# LKS_EVB_MVPOW_V4_0.net
KiCad netlist of a schematic drawn in Altium Designer
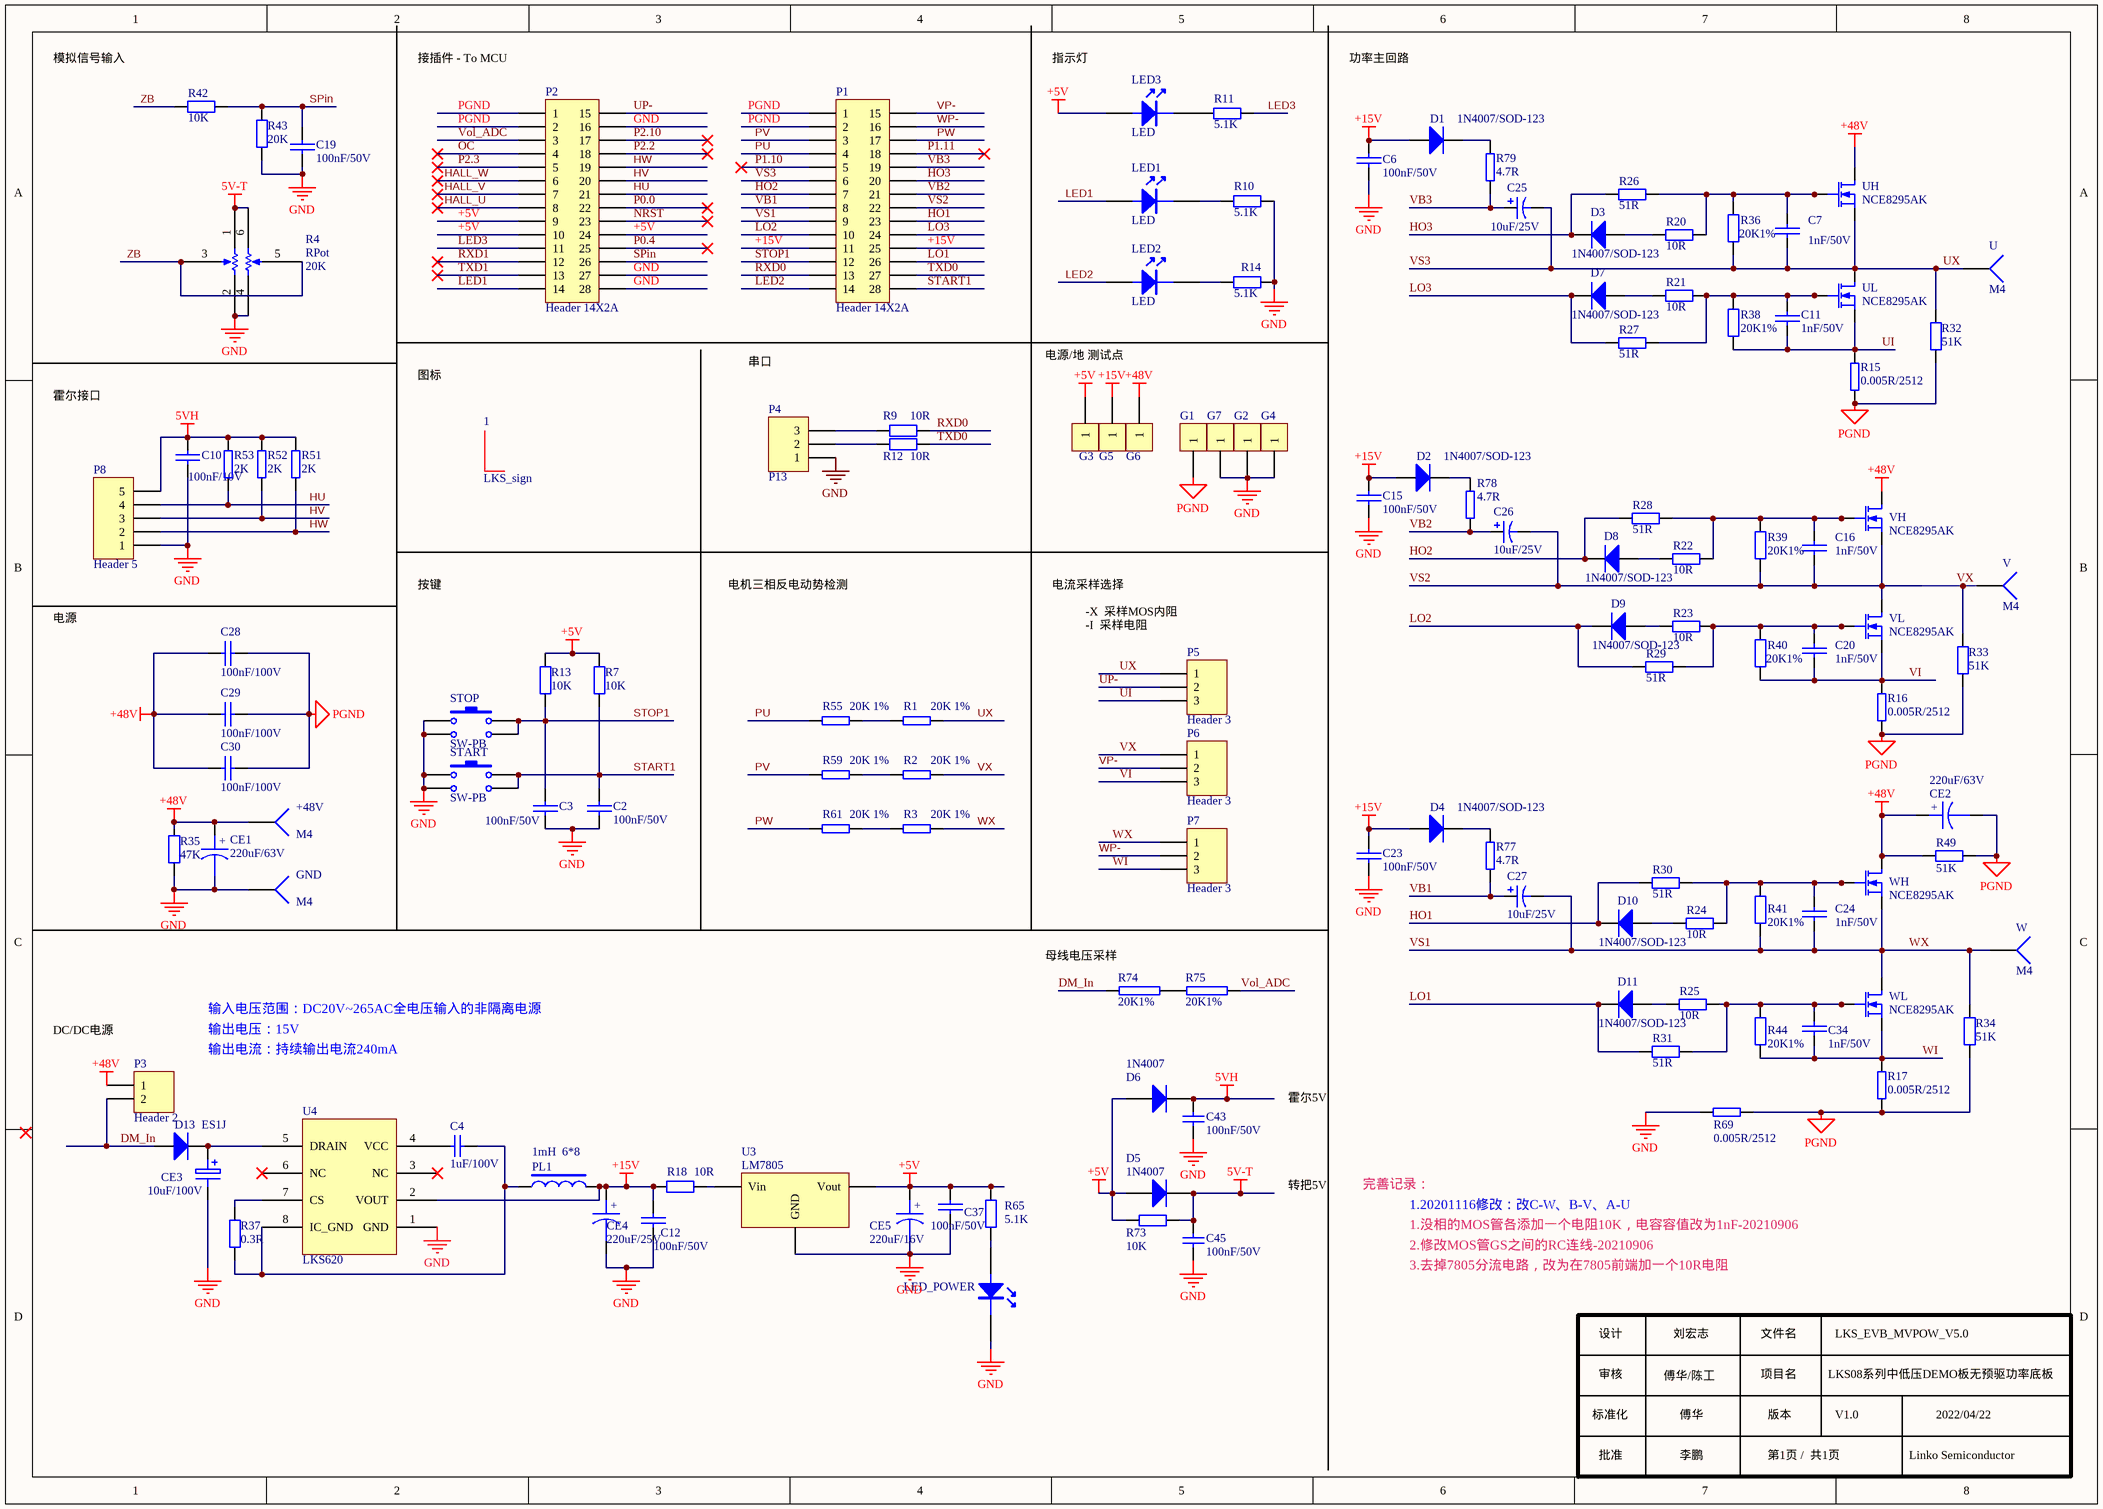
[diagram p0: LKS_EVB_MVPOW_V4.0.SchDoc]

(export (version "E")
  (design (tool "Eeschema 10.0.6"))
  (components
    (comp (ref "+48V")
      (value "M4")
      (footprint "M4_Conector")
      (description "Socket")
      (fields (field (name "PUBLISHER") "Altium Limited"))
      (libsource (lib "*") (part "Socket"))
    )
    (comp (ref "1")
      (value "LKS_sign")
      (footprint "LKS_LOGO2")
      (libsource (lib "linko sch library") (part "LKS_sign"))
    )
    (comp (ref "C2")
      (value "100nF/50V")
      (footprint "0603C")
      (description "Capacitor")
      (libsource (lib "GJ-BC-IC") (part "CAP"))
    )
    (comp (ref "C3")
      (value "100nF/50V")
      (footprint "0603C")
      (description "Capacitor")
      (libsource (lib "GJ-BC-IC") (part "CAP"))
    )
    (comp (ref "C4")
      (value "1uF/100V")
      (footprint "1206")
      (description "Capacitor")
      (fields (field (name "PUBLISHER") "Altium Limited"))
      (libsource (lib "Miscellaneous Devices") (part "Cap"))
    )
    (comp (ref "C6")
      (value "100nF/50V")
      (footprint "0603C")
      (description "Capacitor")
      (libsource (lib "*") (part "C"))
    )
    (comp (ref "C7")
      (value "1nF/50V")
      (footprint "0603C")
      (description "Capacitor")
      (libsource (lib "*") (part "CAP"))
    )
    (comp (ref "C10")
      (value "100nF/10V")
      (footprint "0603C")
      (description "Capacitor")
      (libsource (lib "GJ-BC-IC") (part "CAP"))
    )
    (comp (ref "C11")
      (value "1nF/50V")
      (footprint "0603C")
      (description "Capacitor")
      (libsource (lib "*") (part "CAP"))
    )
    (comp (ref "C12")
      (value "100nF/50V")
      (footprint "0603C")
      (description "Capacitor")
      (libsource (lib "") (part "CAP_1"))
    )
    (comp (ref "C15")
      (value "100nF/50V")
      (footprint "0603C")
      (description "Capacitor")
      (libsource (lib "*") (part "C"))
    )
    (comp (ref "C16")
      (value "1nF/50V")
      (footprint "0603C")
      (description "Capacitor")
      (libsource (lib "*") (part "CAP"))
    )
    (comp (ref "C19")
      (value "100nF/50V")
      (footprint "0603C")
      (description "Capacitor")
      (libsource (lib "*") (part "C"))
    )
    (comp (ref "C20")
      (value "1nF/50V")
      (footprint "0603C")
      (description "Capacitor")
      (libsource (lib "*") (part "CAP"))
    )
    (comp (ref "C23")
      (value "100nF/50V")
      (footprint "0603C")
      (description "Capacitor")
      (libsource (lib "*") (part "C"))
    )
    (comp (ref "C24")
      (value "1nF/50V")
      (footprint "0603C")
      (description "Capacitor")
      (libsource (lib "*") (part "CAP"))
    )
    (comp (ref "C25")
      (value "10uF/25V")
      (footprint "1206")
      (description "Polarized Capacitor (Radial)")
      (fields (field (name "PUBLISHER") "Altium Limited"))
      (libsource (lib "*") (part "Cap Pol1"))
    )
    (comp (ref "C26")
      (value "10uF/25V")
      (footprint "1206")
      (description "Polarized Capacitor (Radial)")
      (fields (field (name "PUBLISHER") "Altium Limited"))
      (libsource (lib "*") (part "Cap Pol1"))
    )
    (comp (ref "C27")
      (value "10uF/25V")
      (footprint "1206")
      (description "Polarized Capacitor (Radial)")
      (fields (field (name "PUBLISHER") "Altium Limited"))
      (libsource (lib "*") (part "Cap Pol1"))
    )
    (comp (ref "C28")
      (value "100nF/100V")
      (footprint "0805C")
      (description "Capacitor")
      (libsource (lib "") (part "CAP_1"))
    )
    (comp (ref "C29")
      (value "100nF/100V")
      (footprint "0805C")
      (description "Capacitor")
      (libsource (lib "") (part "CAP_1"))
    )
    (comp (ref "C30")
      (value "100nF/100V")
      (footprint "0805C")
      (description "Capacitor")
      (libsource (lib "") (part "CAP_1"))
    )
    (comp (ref "C34")
      (value "1nF/50V")
      (footprint "0603C")
      (description "Capacitor")
      (libsource (lib "*") (part "CAP"))
    )
    (comp (ref "C37")
      (value "100nF/50V")
      (footprint "0603C")
      (description "Capacitor")
      (libsource (lib "*") (part "C"))
    )
    (comp (ref "C43")
      (value "100nF/50V")
      (footprint "0603C")
      (description "Capacitor")
      (fields (field (name "PUBLISHER") "Altium Limited"))
      (libsource (lib "Miscellaneous Devices") (part "Cap"))
    )
    (comp (ref "C45")
      (value "100nF/50V")
      (footprint "0603C")
      (description "Capacitor")
      (fields (field (name "PUBLISHER") "Altium Limited"))
      (libsource (lib "Miscellaneous Devices") (part "Cap"))
    )
    (comp (ref "CE1")
      (value "220uF/63V")
      (footprint "220UF/63V 12.5*12.5")
      (description "Capacitor---电解电容")
      (libsource (lib "LINKO_V1.0") (part "Capacitor Pol"))
    )
    (comp (ref "CE2")
      (value "220uF/63V")
      (footprint "220UF/63V 12.5*12.5")
      (description "Capacitor---电解电容")
      (libsource (lib "LINKO_V1.0") (part "Capacitor Pol"))
    )
    (comp (ref "CE3")
      (value "10uF/100V")
      (footprint "220UF/25V paster8*10")
      (description "Electrolytic Capacitor")
      (libsource (lib "*") (part "CD"))
    )
    (comp (ref "CE4")
      (value "220uF/25V")
      (footprint "220UF/25V 8*10")
      (description "Capacitor---电解电容")
      (libsource (lib "LINKO_V1.0") (part "Capacitor Pol"))
    )
    (comp (ref "CE5")
      (value "220uF/16V")
      (footprint "220UF/16V 6.3*7.7")
      (description "Capacitor---电解电容")
      (libsource (lib "LINKO_V1.0") (part "Capacitor Pol"))
    )
    (comp (ref "D1")
      (value "1N4007/SOD-123")
      (footprint "SOD123")
      (description "Default Diode")
      (fields (field (name "PUBLISHER") "Altium Limited"))
      (libsource (lib "*") (part "Diode"))
    )
    (comp (ref "D2")
      (value "1N4007/SOD-123")
      (footprint "SOD123")
      (description "Default Diode")
      (fields (field (name "PUBLISHER") "Altium Limited"))
      (libsource (lib "*") (part "Diode"))
    )
    (comp (ref "D3")
      (value "1N4007/SOD-123")
      (footprint "SOD123")
      (description "Default Diode")
      (fields (field (name "PUBLISHER") "Altium Limited"))
      (libsource (lib "*") (part "Diode"))
    )
    (comp (ref "D4")
      (value "1N4007/SOD-123")
      (footprint "SOD123")
      (description "Default Diode")
      (fields (field (name "PUBLISHER") "Altium Limited"))
      (libsource (lib "*") (part "Diode"))
    )
    (comp (ref "D5")
      (value "1N4007")
      (footprint "D1206")
      (description "1 Amp General Purpose Rectifier")
      (fields (field (name "PUBLISHER") "Altium Limited"))
      (libsource (lib "Miscellaneous Devices") (part "Diode 1N4007"))
    )
    (comp (ref "D6")
      (value "1N4007")
      (footprint "D1206")
      (description "1 Amp General Purpose Rectifier")
      (fields (field (name "PUBLISHER") "Altium Limited"))
      (libsource (lib "Miscellaneous Devices") (part "Diode 1N4007"))
    )
    (comp (ref "D7")
      (value "1N4007/SOD-123")
      (footprint "SOD123")
      (description "Default Diode")
      (fields (field (name "PUBLISHER") "Altium Limited"))
      (libsource (lib "*") (part "Diode"))
    )
    (comp (ref "D8")
      (value "1N4007/SOD-123")
      (footprint "SOD123")
      (description "Default Diode")
      (fields (field (name "PUBLISHER") "Altium Limited"))
      (libsource (lib "*") (part "Diode"))
    )
    (comp (ref "D9")
      (value "1N4007/SOD-123")
      (footprint "SOD123")
      (description "Default Diode")
      (fields (field (name "PUBLISHER") "Altium Limited"))
      (libsource (lib "*") (part "Diode"))
    )
    (comp (ref "D10")
      (value "1N4007/SOD-123")
      (footprint "SOD123")
      (description "Default Diode")
      (fields (field (name "PUBLISHER") "Altium Limited"))
      (libsource (lib "*") (part "Diode"))
    )
    (comp (ref "D11")
      (value "1N4007/SOD-123")
      (footprint "SOD123")
      (description "Default Diode")
      (fields (field (name "PUBLISHER") "Altium Limited"))
      (libsource (lib "*") (part "Diode"))
    )
    (comp (ref "D13")
      (value "ES1J")
      (footprint "DO-214AC")
      (description "Default Diode")
      (fields (field (name "PUBLISHER") "Altium Limited"))
      (libsource (lib "*") (part "Diode"))
    )
    (comp (ref "G1")
      (value "PAD1.2")
      (footprint "PAD1.2")
      (description "Connector")
      (libsource (lib "*") (part "CON1"))
    )
    (comp (ref "G2")
      (value "PAD1.2")
      (footprint "PAD1.2")
      (description "Connector")
      (libsource (lib "*") (part "CON1"))
    )
    (comp (ref "G3")
      (value "PAD1.2")
      (footprint "PAD1.2")
      (description "Connector")
      (libsource (lib "") (part "CON1_1"))
    )
    (comp (ref "G4")
      (value "PAD1.2")
      (footprint "PAD1.2")
      (description "Connector")
      (libsource (lib "*") (part "CON1"))
    )
    (comp (ref "G5")
      (value "PAD1.2")
      (footprint "PAD1.2")
      (description "Connector")
      (libsource (lib "") (part "CON1_1"))
    )
    (comp (ref "G6")
      (value "PAD1.2")
      (footprint "PAD1.2")
      (description "Connector")
      (libsource (lib "") (part "CON1_1"))
    )
    (comp (ref "G7")
      (value "PAD1.2")
      (footprint "PAD1.2")
      (description "Connector")
      (libsource (lib "*") (part "CON1"))
    )
    (comp (ref "GND")
      (value "M4")
      (footprint "M4_Conector")
      (description "Socket")
      (fields (field (name "PUBLISHER") "Altium Limited"))
      (libsource (lib "*") (part "Socket"))
    )
    (comp (ref "LED1") (value "LED") (footprint "SOD323") (libsource (lib "GJ-BC-IC") (part "LED")))
    (comp (ref "LED2") (value "LED") (footprint "SOD323") (libsource (lib "GJ-BC-IC") (part "LED")))
    (comp (ref "LED3") (value "LED") (footprint "SOD323") (libsource (lib "GJ-BC-IC") (part "LED")))
    (comp (ref "LED_POWER") (value "LED_R") (footprint "SOD323") (libsource (lib "*") (part "LED")))
    (comp (ref "P1")
      (value "Header 14X2A")
      (footprint "HDR2X14_CEN")
      (description "Header, 14-Pin, Dual row")
      (fields (field (name "PUBLISHER") "Altium Limited"))
      (libsource (lib "Miscellaneous Connectors") (part "Header 14X2A"))
    )
    (comp (ref "P2")
      (value "Header 14X2A")
      (footprint "HDR2X14_CEN")
      (description "Header, 14-Pin, Dual row")
      (fields (field (name "PUBLISHER") "Altium Limited"))
      (libsource (lib "Miscellaneous Connectors") (part "Header 14X2A"))
    )
    (comp (ref "P3")
      (value "Header 2")
      (footprint "HDR1X2")
      (description "Header, 2-Pin")
      (fields (field (name "PUBLISHER") "Altium Limited"))
      (libsource (lib "Miscellaneous Connectors") (part "Header 2"))
    )
    (comp (ref "P4")
      (value "P13")
      (footprint "2.54-XH-3A-180")
      (description "Header, 3-Pin")
      (fields (field (name "PUBLISHER") "Altium Limited"))
      (libsource (lib "") (part "Header 3_1"))
    )
    (comp (ref "P5")
      (value "Header 3")
      (footprint "HDR1X3")
      (description "Header, 3-Pin")
      (fields (field (name "PUBLISHER") "Altium Limited"))
      (libsource (lib "Miscellaneous Connectors") (part "Header 3"))
    )
    (comp (ref "P6")
      (value "Header 3")
      (footprint "HDR1X3")
      (description "Header, 3-Pin")
      (fields (field (name "PUBLISHER") "Altium Limited"))
      (libsource (lib "Miscellaneous Connectors") (part "Header 3"))
    )
    (comp (ref "P7")
      (value "Header 3")
      (footprint "HDR1X3")
      (description "Header, 3-Pin")
      (fields (field (name "PUBLISHER") "Altium Limited"))
      (libsource (lib "Miscellaneous Connectors") (part "Header 3"))
    )
    (comp (ref "P8")
      (value "Header 5")
      (footprint "2.54-XH-5A-180")
      (description "Header, 5-Pin")
      (fields (field (name "PUBLISHER") "Altium Limited"))
      (libsource (lib "Miscellaneous Connectors") (part "Header 5"))
    )
    (comp (ref "PL1") (value "1mH  6*8") (footprint "L_DIP_6*8MM") (libsource (lib "*") (part "L")))
    (comp (ref "R1") (value "20K 1%") (footprint "0805R") (libsource (lib "HenterLi") (part "RES/1")))
    (comp (ref "R2") (value "20K 1%") (footprint "0805R") (libsource (lib "HenterLi") (part "RES/1")))
    (comp (ref "R3") (value "20K 1%") (footprint "0805R") (libsource (lib "HenterLi") (part "RES/1")))
    (comp (ref "R4")
      (value "RPot")
      (footprint "RK097-W-1")
      (description "Potentiometer")
      (fields (field (name "ALTIUM_VALUE") "20K") (field (name "PUBLISHER") "Altium Limited"))
      (libsource (lib "LKS_DEMO_V5.0") (part "RPot"))
    )
    (comp (ref "R7")
      (value "10K")
      (footprint "0603R")
      (description "Resistor")
      (fields (field (name "PUBLISHER") "Altium Limited"))
      (libsource (lib "") (part "Res2_1"))
    )
    (comp (ref "R9")
      (value "10R")
      (footprint "0603R")
      (description "Resistor")
      (fields (field (name "PUBLISHER") "Altium Limited"))
      (libsource (lib "Miscellaneous Devices") (part "Res2"))
    )
    (comp (ref "R10")
      (value "5.1K")
      (footprint "0603R")
      (description "Resistor")
      (fields (field (name "PUBLISHER") "Altium Limited"))
      (libsource (lib "") (part "Res2_2"))
    )
    (comp (ref "R11")
      (value "5.1K")
      (footprint "0603R")
      (description "Resistor")
      (fields (field (name "PUBLISHER") "Altium Limited"))
      (libsource (lib "") (part "Res2_2"))
    )
    (comp (ref "R12")
      (value "10R")
      (footprint "0603R")
      (description "Resistor")
      (fields (field (name "PUBLISHER") "Altium Limited"))
      (libsource (lib "") (part "Res2_1"))
    )
    (comp (ref "R13")
      (value "10K")
      (footprint "0603R")
      (description "Resistor")
      (fields (field (name "PUBLISHER") "Altium Limited"))
      (libsource (lib "GJ-BC-IC") (part "Res2"))
    )
    (comp (ref "R14")
      (value "5.1K")
      (footprint "0603R")
      (description "Resistor")
      (fields (field (name "PUBLISHER") "Altium Limited"))
      (libsource (lib "") (part "Res2_2"))
    )
    (comp (ref "R15") (value "0.005R/2512") (footprint "2512") (libsource (lib "*") (part "RES2短")))
    (comp (ref "R16") (value "0.005R/2512") (footprint "2512") (libsource (lib "*") (part "RES2短")))
    (comp (ref "R17") (value "0.005R/2512") (footprint "2512") (libsource (lib "*") (part "RES2短")))
    (comp (ref "R18")
      (value "10R")
      (footprint "1206R")
      (description "Resistor")
      (fields (field (name "PUBLISHER") "Altium Limited"))
      (libsource (lib "LINKO_V1.0") (part "Res"))
    )
    (comp (ref "R20")
      (value "10R")
      (footprint "0805R")
      (description "Resistor")
      (fields (field (name "PUBLISHER") "Altium Limited"))
      (libsource (lib "") (part "1Res_1"))
    )
    (comp (ref "R21")
      (value "10R")
      (footprint "0805R")
      (description "Resistor")
      (fields (field (name "PUBLISHER") "Altium Limited"))
      (libsource (lib "") (part "1Res_1"))
    )
    (comp (ref "R22")
      (value "10R")
      (footprint "0805R")
      (description "Resistor")
      (fields (field (name "PUBLISHER") "Altium Limited"))
      (libsource (lib "") (part "1Res_1"))
    )
    (comp (ref "R23")
      (value "10R")
      (footprint "0805R")
      (description "Resistor")
      (fields (field (name "PUBLISHER") "Altium Limited"))
      (libsource (lib "") (part "1Res_1"))
    )
    (comp (ref "R24")
      (value "10R")
      (footprint "0805R")
      (description "Resistor")
      (fields (field (name "PUBLISHER") "Altium Limited"))
      (libsource (lib "") (part "1Res_1"))
    )
    (comp (ref "R25")
      (value "10R")
      (footprint "0805R")
      (description "Resistor")
      (fields (field (name "PUBLISHER") "Altium Limited"))
      (libsource (lib "") (part "1Res_1"))
    )
    (comp (ref "R26")
      (value "51R")
      (footprint "0805R")
      (description "Resistor")
      (fields (field (name "PUBLISHER") "Altium Limited"))
      (libsource (lib "LINKO_V1.0") (part "Res"))
    )
    (comp (ref "R27")
      (value "51R")
      (footprint "0805R")
      (description "Resistor")
      (fields (field (name "PUBLISHER") "Altium Limited"))
      (libsource (lib "LINKO_V1.0") (part "1Res"))
    )
    (comp (ref "R28")
      (value "51R")
      (footprint "0805R")
      (description "Resistor")
      (fields (field (name "PUBLISHER") "Altium Limited"))
      (libsource (lib "LINKO_V1.0") (part "1Res"))
    )
    (comp (ref "R29")
      (value "51R")
      (footprint "0805R")
      (description "Resistor")
      (fields (field (name "PUBLISHER") "Altium Limited"))
      (libsource (lib "LINKO_V1.0") (part "1Res"))
    )
    (comp (ref "R30")
      (value "51R")
      (footprint "0805R")
      (description "Resistor")
      (fields (field (name "PUBLISHER") "Altium Limited"))
      (libsource (lib "LINKO_V1.0") (part "1Res"))
    )
    (comp (ref "R31")
      (value "51R")
      (footprint "0805R")
      (description "Resistor")
      (fields (field (name "PUBLISHER") "Altium Limited"))
      (libsource (lib "LINKO_V1.0") (part "1Res"))
    )
    (comp (ref "R32")
      (value "51K")
      (footprint "0805R")
      (description "Resistor")
      (fields (field (name "PUBLISHER") "Altium Limited"))
      (libsource (lib "") (part "1Res_2"))
    )
    (comp (ref "R33")
      (value "51K")
      (footprint "0805R")
      (description "Resistor")
      (fields (field (name "PUBLISHER") "Altium Limited"))
      (libsource (lib "") (part "1Res_2"))
    )
    (comp (ref "R34")
      (value "51K")
      (footprint "0805R")
      (description "Resistor")
      (fields (field (name "PUBLISHER") "Altium Limited"))
      (libsource (lib "") (part "1Res_2"))
    )
    (comp (ref "R35")
      (value "47K")
      (footprint "1206R")
      (description "Resistor")
      (fields (field (name "PUBLISHER") "Altium Limited"))
      (libsource (lib "") (part "Res_2"))
    )
    (comp (ref "R36")
      (value "20K1%")
      (footprint "0603R")
      (description "Resistor")
      (fields (field (name "PUBLISHER") "Altium Limited"))
      (libsource (lib "") (part "Res_1"))
    )
    (comp (ref "R37")
      (value "0.3R")
      (footprint "1206")
      (description "Resistor")
      (fields (field (name "PUBLISHER") "Altium Limited"))
      (libsource (lib "") (part "Res2_1"))
    )
    (comp (ref "R38")
      (value "20K1%")
      (footprint "0603R")
      (description "Resistor")
      (fields (field (name "PUBLISHER") "Altium Limited"))
      (libsource (lib "") (part "Res_1"))
    )
    (comp (ref "R39")
      (value "20K1%")
      (footprint "0603R")
      (description "Resistor")
      (fields (field (name "PUBLISHER") "Altium Limited"))
      (libsource (lib "") (part "Res_1"))
    )
    (comp (ref "R40")
      (value "20K1%")
      (footprint "0603R")
      (description "Resistor")
      (fields (field (name "PUBLISHER") "Altium Limited"))
      (libsource (lib "") (part "Res_1"))
    )
    (comp (ref "R41")
      (value "20K1%")
      (footprint "0603R")
      (description "Resistor")
      (fields (field (name "PUBLISHER") "Altium Limited"))
      (libsource (lib "") (part "Res_1"))
    )
    (comp (ref "R42")
      (value "10K")
      (footprint "0603R")
      (description "Resistor")
      (fields (field (name "PUBLISHER") "Altium Limited"))
      (libsource (lib "LINKO_V1.0") (part "Res"))
    )
    (comp (ref "R43")
      (value "20K")
      (footprint "0603R")
      (description "Resistor")
      (fields (field (name "PUBLISHER") "Altium Limited"))
      (libsource (lib "") (part "Res_1"))
    )
    (comp (ref "R44")
      (value "20K1%")
      (footprint "0603R")
      (description "Resistor")
      (fields (field (name "PUBLISHER") "Altium Limited"))
      (libsource (lib "") (part "Res_1"))
    )
    (comp (ref "R49")
      (value "51K")
      (footprint "0805R")
      (description "Resistor")
      (fields (field (name "PUBLISHER") "Altium Limited"))
      (libsource (lib "LINKO_V1.0") (part "1Res"))
    )
    (comp (ref "R51") (value "2K") (footprint "0603R") (libsource (lib "") (part "RES/1_1")))
    (comp (ref "R52") (value "2K") (footprint "0603R") (libsource (lib "") (part "RES/1_1")))
    (comp (ref "R53") (value "2K") (footprint "0603R") (libsource (lib "") (part "RES/1_1")))
    (comp (ref "R55") (value "20K 1%") (footprint "0805R") (libsource (lib "HenterLi") (part "RES/1")))
    (comp (ref "R59") (value "20K 1%") (footprint "0805R") (libsource (lib "HenterLi") (part "RES/1")))
    (comp (ref "R61") (value "20K 1%") (footprint "0805R") (libsource (lib "HenterLi") (part "RES/1")))
    (comp (ref "R65")
      (value "5.1K")
      (footprint "0603R")
      (description "Resistor")
      (fields (field (name "PUBLISHER") "Altium Limited"))
      (libsource (lib "Miscellaneous Devices") (part "Res2"))
    )
    (comp (ref "R69") (value "0.005R/2512") (footprint "2512") (libsource (lib "*") (part "RES2短")))
    (comp (ref "R73")
      (value "10K")
      (footprint "0603R")
      (description "Resistor")
      (fields (field (name "PUBLISHER") "Altium Limited"))
      (libsource (lib "") (part "Res2_2"))
    )
    (comp (ref "R74") (value "20K1%") (footprint "0603R") (libsource (lib "*") (part "R")))
    (comp (ref "R75") (value "20K1%") (footprint "0603R") (libsource (lib "*") (part "R")))
    (comp (ref "R77") (value "4.7R") (footprint "0805r") (libsource (lib "*") (part "RES2短")))
    (comp (ref "R78") (value "4.7R") (footprint "0805r") (libsource (lib "*") (part "RES2短")))
    (comp (ref "R79") (value "4.7R") (footprint "0805r") (libsource (lib "*") (part "RES2短")))
    (comp (ref "START")
      (value "SW-PB")
      (footprint "SW-PB  12*12")
      (description "Switch")
      (fields (field (name "PUBLISHER") "Altium Limited"))
      (libsource (lib "LKS_DEMO_081_V4.0") (part "SW-PB"))
    )
    (comp (ref "STOP")
      (value "SW-PB")
      (footprint "SW-PB  12*12")
      (description "Switch")
      (fields (field (name "PUBLISHER") "Altium Limited"))
      (libsource (lib "LKS_DEMO_081_V4.0") (part "SW-PB"))
    )
    (comp (ref "U")
      (value "M4")
      (footprint "M4_Conector")
      (description "Socket")
      (fields (field (name "PUBLISHER") "Altium Limited"))
      (libsource (lib "*") (part "Socket"))
    )
    (comp (ref "U3")
      (value "LM7805")
      (footprint "linko pcb library:SOT-89")
      (libsource (lib "*") (part "VOL-78"))
    )
    (comp (ref "U4") (value "LKS620") (footprint "SO-8") (libsource (lib "081-620") (part "LKS620")))
    (comp (ref "UH")
      (value "NCE8295AK")
      (footprint "TO-252")
      (libsource (lib "POWER-conponent") (part "MOS"))
    )
    (comp (ref "UL")
      (value "NCE8295AK")
      (footprint "TO-252")
      (libsource (lib "POWER-conponent") (part "MOS"))
    )
    (comp (ref "V")
      (value "M4")
      (footprint "M4_Conector")
      (description "Socket")
      (fields (field (name "PUBLISHER") "Altium Limited"))
      (libsource (lib "*") (part "Socket"))
    )
    (comp (ref "VH")
      (value "NCE8295AK")
      (footprint "TO-252")
      (libsource (lib "POWER-conponent") (part "MOS"))
    )
    (comp (ref "VL")
      (value "NCE8295AK")
      (footprint "TO-252")
      (libsource (lib "POWER-conponent") (part "MOS"))
    )
    (comp (ref "W")
      (value "M4")
      (footprint "M4_Conector")
      (description "Socket")
      (fields (field (name "PUBLISHER") "Altium Limited"))
      (libsource (lib "*") (part "Socket"))
    )
    (comp (ref "WH")
      (value "NCE8295AK")
      (footprint "TO-252")
      (libsource (lib "POWER-conponent") (part "MOS"))
    )
    (comp (ref "WL")
      (value "NCE8295AK")
      (footprint "TO-252")
      (libsource (lib "POWER-conponent") (part "MOS"))
    )
  )
  (nets
    (net (code "1") (name "+5V") (class "Default")
      (node (ref "C37") (pin "2") (pinfunction "2_2") (pintype "passive"))
      (node (ref "CE5") (pin "1") (pinfunction "1_1") (pintype "passive"))
      (node (ref "D5") (pin "1") (pinfunction "A_1") (pintype "passive"))
      (node (ref "D6") (pin "1") (pinfunction "A_1") (pintype "passive"))
      (node (ref "G3") (pin "1") (pinfunction "1_1") (pintype "passive"))
      (node (ref "LED3") (pin "1") (pinfunction "A_1") (pintype "passive"))
      (node (ref "P2") (pin "10") (pinfunction "10_10") (pintype "passive"))
      (node (ref "P2") (pin "24") (pinfunction "24_24") (pintype "passive"))
      (node (ref "P2") (pin "9") (pinfunction "9_9") (pintype "passive"))
      (node (ref "R13") (pin "2") (pinfunction "2_2") (pintype "passive"))
      (node (ref "R65") (pin "1") (pinfunction "1_1") (pintype "passive"))
      (node (ref "R7") (pin "1") (pinfunction "1_1") (pintype "passive"))
      (node (ref "R73") (pin "1") (pinfunction "1_1") (pintype "passive"))
      (node (ref "U3") (pin "1") (pinfunction "Vout_1") (pintype "passive"))
    )
    (net (code "2") (name "+15V") (class "Default")
      (node (ref "C12") (pin "1") (pinfunction "1_1") (pintype "passive"))
      (node (ref "C15") (pin "2") (pinfunction "2_2") (pintype "passive"))
      (node (ref "C23") (pin "2") (pinfunction "2_2") (pintype "passive"))
      (node (ref "C6") (pin "2") (pinfunction "2_2") (pintype "passive"))
      (node (ref "CE4") (pin "1") (pinfunction "1_1") (pintype "passive"))
      (node (ref "D1") (pin "1") (pinfunction "A_1") (pintype "passive"))
      (node (ref "D2") (pin "1") (pinfunction "A_1") (pintype "passive"))
      (node (ref "D4") (pin "1") (pinfunction "A_1") (pintype "passive"))
      (node (ref "G5") (pin "1") (pinfunction "1_1") (pintype "passive"))
      (node (ref "P1") (pin "11") (pinfunction "11_11") (pintype "passive"))
      (node (ref "P1") (pin "25") (pinfunction "25_25") (pintype "passive"))
      (node (ref "PL1") (pin "1") (pinfunction "1_1") (pintype "passive"))
      (node (ref "R18") (pin "1") (pinfunction "1_1") (pintype "passive"))
      (node (ref "U4") (pin "2") (pinfunction "VOUT_2") (pintype "passive"))
    )
    (net (code "3") (name "+48V") (class "Default")
      (node (ref "+48V") (pin "1") (pinfunction "1_1") (pintype "passive"))
      (node (ref "C28") (pin "2") (pinfunction "2_2") (pintype "passive"))
      (node (ref "C29") (pin "2") (pinfunction "2_2") (pintype "passive"))
      (node (ref "C30") (pin "2") (pinfunction "2_2") (pintype "passive"))
      (node (ref "CE1") (pin "1") (pinfunction "1_1") (pintype "passive"))
      (node (ref "CE2") (pin "1") (pinfunction "1_1") (pintype "passive"))
      (node (ref "G6") (pin "1") (pinfunction "1_1") (pintype "passive"))
      (node (ref "P3") (pin "1") (pinfunction "1_1") (pintype "passive"))
      (node (ref "R35") (pin "1") (pinfunction "1_1") (pintype "passive"))
      (node (ref "R49") (pin "1") (pinfunction "1_1") (pintype "passive"))
      (node (ref "UH") (pin "2") (pinfunction "D_2") (pintype "passive"))
      (node (ref "VH") (pin "2") (pinfunction "D_2") (pintype "passive"))
      (node (ref "WH") (pin "2") (pinfunction "D_2") (pintype "passive"))
    )
    (net (code "4") (name "/DM_In") (class "Default")
      (node (ref "D13") (pin "1") (pinfunction "A_1") (pintype "passive"))
      (node (ref "P3") (pin "2") (pinfunction "2_2") (pintype "passive"))
      (node (ref "R74") (pin "1") (pinfunction "1_1") (pintype "passive"))
    )
    (net (code "5") (name "/HALL_U") (class "Default")
      (node (ref "P2") (pin "8") (pinfunction "8_8") (pintype "passive+no_connect"))
    )
    (net (code "6") (name "/HALL_V") (class "Default")
      (node (ref "P2") (pin "7") (pinfunction "7_7") (pintype "passive+no_connect"))
    )
    (net (code "7") (name "/HALL_W") (class "Default")
      (node (ref "P2") (pin "6") (pinfunction "6_6") (pintype "passive+no_connect"))
    )
    (net (code "8") (name "/HO1") (class "Default")
      (node (ref "D10") (pin "2") (pinfunction "K_2") (pintype "passive"))
      (node (ref "P1") (pin "23") (pinfunction "23_23") (pintype "passive"))
      (node (ref "R30") (pin "1") (pinfunction "1_1") (pintype "passive"))
    )
    (net (code "9") (name "/HO2") (class "Default")
      (node (ref "D8") (pin "2") (pinfunction "K_2") (pintype "passive"))
      (node (ref "P1") (pin "7") (pinfunction "7_7") (pintype "passive"))
      (node (ref "R28") (pin "1") (pinfunction "1_1") (pintype "passive"))
    )
    (net (code "10") (name "/HO3") (class "Default")
      (node (ref "D3") (pin "2") (pinfunction "K_2") (pintype "passive"))
      (node (ref "P1") (pin "20") (pinfunction "20_20") (pintype "passive"))
      (node (ref "R26") (pin "1") (pinfunction "1_1") (pintype "passive"))
    )
    (net (code "11") (name "/HU") (class "Default")
      (node (ref "P2") (pin "21") (pinfunction "21_21") (pintype "passive"))
      (node (ref "P8") (pin "4") (pinfunction "4_4") (pintype "passive"))
      (node (ref "R53") (pin "1") (pinfunction "1_1") (pintype "passive"))
    )
    (net (code "12") (name "/HV") (class "Default")
      (node (ref "P2") (pin "20") (pinfunction "20_20") (pintype "passive"))
      (node (ref "P8") (pin "3") (pinfunction "3_3") (pintype "passive"))
      (node (ref "R52") (pin "1") (pinfunction "1_1") (pintype "passive"))
    )
    (net (code "13") (name "/HW") (class "Default")
      (node (ref "P2") (pin "19") (pinfunction "19_19") (pintype "passive"))
      (node (ref "P8") (pin "2") (pinfunction "2_2") (pintype "passive"))
      (node (ref "R51") (pin "1") (pinfunction "1_1") (pintype "passive"))
    )
    (net (code "14") (name "/LED1") (class "Default")
      (node (ref "LED1") (pin "1") (pinfunction "A_1") (pintype "passive"))
      (node (ref "P2") (pin "14") (pinfunction "14_14") (pintype "passive"))
    )
    (net (code "15") (name "/LED2") (class "Default")
      (node (ref "LED2") (pin "1") (pinfunction "A_1") (pintype "passive"))
      (node (ref "P1") (pin "14") (pinfunction "14_14") (pintype "passive"))
    )
    (net (code "16") (name "/LED3") (class "Default")
      (node (ref "P2") (pin "11") (pinfunction "11_11") (pintype "passive"))
      (node (ref "R11") (pin "2") (pinfunction "2_2") (pintype "passive"))
    )
    (net (code "17") (name "/LO1") (class "Default")
      (node (ref "D11") (pin "2") (pinfunction "K_2") (pintype "passive"))
      (node (ref "P1") (pin "26") (pinfunction "26_26") (pintype "passive"))
      (node (ref "R31") (pin "1") (pinfunction "1_1") (pintype "passive"))
    )
    (net (code "18") (name "/LO2") (class "Default")
      (node (ref "D9") (pin "2") (pinfunction "K_2") (pintype "passive"))
      (node (ref "P1") (pin "10") (pinfunction "10_10") (pintype "passive"))
      (node (ref "R29") (pin "1") (pinfunction "1_1") (pintype "passive"))
    )
    (net (code "19") (name "/LO3") (class "Default")
      (node (ref "D7") (pin "2") (pinfunction "K_2") (pintype "passive"))
      (node (ref "P1") (pin "24") (pinfunction "24_24") (pintype "passive"))
      (node (ref "R27") (pin "1") (pinfunction "1_1") (pintype "passive"))
    )
    (net (code "20") (name "/NRST") (class "Default")
      (node (ref "P2") (pin "23") (pinfunction "23_23") (pintype "passive+no_connect"))
    )
    (net (code "21") (name "/OC") (class "Default")
      (node (ref "P2") (pin "4") (pinfunction "4_4") (pintype "passive+no_connect"))
    )
    (net (code "22") (name "/P0.0") (class "Default")
      (node (ref "P2") (pin "22") (pinfunction "22_22") (pintype "passive+no_connect"))
    )
    (net (code "23") (name "/P0.4") (class "Default")
      (node (ref "P2") (pin "25") (pinfunction "25_25") (pintype "passive+no_connect"))
    )
    (net (code "24") (name "/P1.10") (class "Default")
      (node (ref "P1") (pin "5") (pinfunction "5_5") (pintype "passive+no_connect"))
    )
    (net (code "25") (name "/P1.11") (class "Default")
      (node (ref "P1") (pin "18") (pinfunction "18_18") (pintype "passive+no_connect"))
    )
    (net (code "26") (name "/P2.2") (class "Default")
      (node (ref "P2") (pin "18") (pinfunction "18_18") (pintype "passive+no_connect"))
    )
    (net (code "27") (name "/P2.3") (class "Default")
      (node (ref "P2") (pin "5") (pinfunction "5_5") (pintype "passive+no_connect"))
    )
    (net (code "28") (name "/P2.10") (class "Default")
      (node (ref "P2") (pin "17") (pinfunction "17_17") (pintype "passive+no_connect"))
    )
    (net (code "29") (name "/PU") (class "Default")
      (node (ref "P1") (pin "4") (pinfunction "4_4") (pintype "passive"))
      (node (ref "R55") (pin "1") (pinfunction "1_1") (pintype "passive"))
    )
    (net (code "30") (name "/PV") (class "Default")
      (node (ref "P1") (pin "3") (pinfunction "3_3") (pintype "passive"))
      (node (ref "R59") (pin "1") (pinfunction "1_1") (pintype "passive"))
    )
    (net (code "31") (name "/PW") (class "Default")
      (node (ref "P1") (pin "17") (pinfunction "17_17") (pintype "passive"))
      (node (ref "R61") (pin "1") (pinfunction "1_1") (pintype "passive"))
    )
    (net (code "32") (name "/RXD0") (class "Default")
      (node (ref "P1") (pin "13") (pinfunction "13_13") (pintype "passive"))
      (node (ref "R9") (pin "1") (pinfunction "1_1") (pintype "passive"))
    )
    (net (code "33") (name "/RXD1") (class "Default")
      (node (ref "P2") (pin "12") (pinfunction "12_12") (pintype "passive+no_connect"))
    )
    (net (code "34") (name "/SPin") (class "Default")
      (node (ref "C19") (pin "2") (pinfunction "2_2") (pintype "passive"))
      (node (ref "P2") (pin "26") (pinfunction "26_26") (pintype "passive"))
      (node (ref "R42") (pin "2") (pinfunction "2_2") (pintype "passive"))
      (node (ref "R43") (pin "2") (pinfunction "2_2") (pintype "passive"))
    )
    (net (code "35") (name "/START1") (class "Default")
      (node (ref "C2") (pin "2") (pinfunction "2_2") (pintype "passive"))
      (node (ref "P1") (pin "28") (pinfunction "28_28") (pintype "passive"))
      (node (ref "R7") (pin "2") (pinfunction "2_2") (pintype "passive"))
      (node (ref "START") (pin "2") (pinfunction "2_2") (pintype "passive"))
      (node (ref "START") (pin "4") (pinfunction "4_4") (pintype "passive"))
    )
    (net (code "36") (name "/STOP1") (class "Default")
      (node (ref "C3") (pin "1") (pinfunction "1_1") (pintype "passive"))
      (node (ref "P1") (pin "12") (pinfunction "12_12") (pintype "passive"))
      (node (ref "R13") (pin "1") (pinfunction "1_1") (pintype "passive"))
      (node (ref "STOP") (pin "2") (pinfunction "2_2") (pintype "passive"))
      (node (ref "STOP") (pin "4") (pinfunction "4_4") (pintype "passive"))
    )
    (net (code "37") (name "/TXD0") (class "Default")
      (node (ref "P1") (pin "27") (pinfunction "27_27") (pintype "passive"))
      (node (ref "R12") (pin "2") (pinfunction "2_2") (pintype "passive"))
    )
    (net (code "38") (name "/TXD1") (class "Default")
      (node (ref "P2") (pin "13") (pinfunction "13_13") (pintype "passive+no_connect"))
    )
    (net (code "39") (name "/UI") (class "Default")
      (node (ref "C11") (pin "2") (pinfunction "2_2") (pintype "passive"))
      (node (ref "P5") (pin "3") (pinfunction "3_3") (pintype "passive"))
      (node (ref "R15") (pin "1") (pinfunction "1_1") (pintype "passive"))
      (node (ref "R38") (pin "1") (pinfunction "1_1") (pintype "passive"))
      (node (ref "UL") (pin "3") (pinfunction "S_3") (pintype "passive"))
    )
    (net (code "40") (name "/UP-") (class "Default")
      (node (ref "P2") (pin "15") (pinfunction "15_15") (pintype "passive"))
      (node (ref "P5") (pin "2") (pinfunction "2_2") (pintype "passive"))
    )
    (net (code "41") (name "/UX") (class "Default")
      (node (ref "C25") (pin "2") (pinfunction "2_2") (pintype "passive"))
      (node (ref "C7") (pin "2") (pinfunction "2_2") (pintype "passive"))
      (node (ref "P1") (pin "6") (pinfunction "6_6") (pintype "passive"))
      (node (ref "P5") (pin "1") (pinfunction "1_1") (pintype "passive"))
      (node (ref "R1") (pin "2") (pinfunction "2_2") (pintype "passive"))
      (node (ref "R32") (pin "2") (pinfunction "2_2") (pintype "passive"))
      (node (ref "R36") (pin "1") (pinfunction "1_1") (pintype "passive"))
      (node (ref "U") (pin "1") (pinfunction "1_1") (pintype "passive"))
      (node (ref "UH") (pin "3") (pinfunction "S_3") (pintype "passive"))
      (node (ref "UL") (pin "2") (pinfunction "D_2") (pintype "passive"))
    )
    (net (code "42") (name "/VB1") (class "Default")
      (node (ref "C27") (pin "1") (pinfunction "1_1") (pintype "passive"))
      (node (ref "P1") (pin "8") (pinfunction "8_8") (pintype "passive"))
      (node (ref "R77") (pin "1") (pinfunction "1_1") (pintype "passive"))
    )
    (net (code "43") (name "/VB2") (class "Default")
      (node (ref "C26") (pin "1") (pinfunction "1_1") (pintype "passive"))
      (node (ref "P1") (pin "21") (pinfunction "21_21") (pintype "passive"))
      (node (ref "R78") (pin "1") (pinfunction "1_1") (pintype "passive"))
    )
    (net (code "44") (name "/VB3") (class "Default")
      (node (ref "C25") (pin "1") (pinfunction "1_1") (pintype "passive"))
      (node (ref "P1") (pin "19") (pinfunction "19_19") (pintype "passive"))
      (node (ref "R79") (pin "1") (pinfunction "1_1") (pintype "passive"))
    )
    (net (code "45") (name "/VI") (class "Default")
      (node (ref "C20") (pin "2") (pinfunction "2_2") (pintype "passive"))
      (node (ref "P6") (pin "3") (pinfunction "3_3") (pintype "passive"))
      (node (ref "R16") (pin "2") (pinfunction "2_2") (pintype "passive"))
      (node (ref "R40") (pin "1") (pinfunction "1_1") (pintype "passive"))
      (node (ref "VL") (pin "3") (pinfunction "S_3") (pintype "passive"))
    )
    (net (code "46") (name "/VP-") (class "Default")
      (node (ref "P1") (pin "15") (pinfunction "15_15") (pintype "passive"))
      (node (ref "P6") (pin "2") (pinfunction "2_2") (pintype "passive"))
    )
    (net (code "47") (name "/VS1") (class "Default")
      (node (ref "C24") (pin "2") (pinfunction "2_2") (pintype "passive"))
      (node (ref "C27") (pin "2") (pinfunction "2_2") (pintype "passive"))
      (node (ref "P1") (pin "9") (pinfunction "9_9") (pintype "passive"))
      (node (ref "P7") (pin "1") (pinfunction "1_1") (pintype "passive"))
      (node (ref "R3") (pin "2") (pinfunction "2_2") (pintype "passive"))
      (node (ref "R34") (pin "2") (pinfunction "2_2") (pintype "passive"))
      (node (ref "R41") (pin "1") (pinfunction "1_1") (pintype "passive"))
      (node (ref "W") (pin "1") (pinfunction "1_1") (pintype "passive"))
      (node (ref "WH") (pin "3") (pinfunction "S_3") (pintype "passive"))
      (node (ref "WL") (pin "2") (pinfunction "D_2") (pintype "passive"))
    )
    (net (code "48") (name "/VS2") (class "Default")
      (node (ref "C16") (pin "2") (pinfunction "2_2") (pintype "passive"))
      (node (ref "C26") (pin "2") (pinfunction "2_2") (pintype "passive"))
      (node (ref "P1") (pin "22") (pinfunction "22_22") (pintype "passive"))
      (node (ref "P6") (pin "1") (pinfunction "1_1") (pintype "passive"))
      (node (ref "R2") (pin "2") (pinfunction "2_2") (pintype "passive"))
      (node (ref "R33") (pin "2") (pinfunction "2_2") (pintype "passive"))
      (node (ref "R39") (pin "1") (pinfunction "1_1") (pintype "passive"))
      (node (ref "V") (pin "1") (pinfunction "1_1") (pintype "passive"))
      (node (ref "VH") (pin "3") (pinfunction "S_3") (pintype "passive"))
      (node (ref "VL") (pin "2") (pinfunction "D_2") (pintype "passive"))
    )
    (net (code "49") (name "/Vol_ADC") (class "Default")
      (node (ref "P2") (pin "3") (pinfunction "3_3") (pintype "passive"))
      (node (ref "R75") (pin "2") (pinfunction "2_2") (pintype "passive"))
    )
    (net (code "50") (name "/WI") (class "Default")
      (node (ref "C34") (pin "2") (pinfunction "2_2") (pintype "passive"))
      (node (ref "P7") (pin "3") (pinfunction "3_3") (pintype "passive"))
      (node (ref "R17") (pin "1") (pinfunction "1_1") (pintype "passive"))
      (node (ref "R44") (pin "1") (pinfunction "1_1") (pintype "passive"))
      (node (ref "WL") (pin "3") (pinfunction "S_3") (pintype "passive"))
    )
    (net (code "51") (name "/WP-") (class "Default")
      (node (ref "P1") (pin "16") (pinfunction "16_16") (pintype "passive"))
      (node (ref "P7") (pin "2") (pinfunction "2_2") (pintype "passive"))
    )
    (net (code "52") (name "/ZB") (class "Default")
      (node (ref "R4") (pin "3") (pinfunction "BOT_3") (pintype "passive"))
      (node (ref "R4") (pin "5") (pinfunction "TAP_5") (pintype "passive"))
      (node (ref "R42") (pin "1") (pinfunction "1_1") (pintype "passive"))
    )
    (net (code "55") (name "5V-T") (class "Default")
      (node (ref "C45") (pin "2") (pinfunction "2_2") (pintype "passive"))
      (node (ref "D5") (pin "2") (pinfunction "K_2") (pintype "passive"))
      (node (ref "R4") (pin "1") (pinfunction "TOP_1") (pintype "passive"))
      (node (ref "R4") (pin "6") (pinfunction "TOP_6") (pintype "passive"))
      (node (ref "R73") (pin "2") (pinfunction "2_2") (pintype "passive"))
    )
    (net (code "56") (name "5VH") (class "Default")
      (node (ref "C10") (pin "1") (pinfunction "1_1") (pintype "passive"))
      (node (ref "C43") (pin "2") (pinfunction "2_2") (pintype "passive"))
      (node (ref "D6") (pin "2") (pinfunction "K_2") (pintype "passive"))
      (node (ref "P8") (pin "5") (pinfunction "5_5") (pintype "passive"))
      (node (ref "R51") (pin "2") (pinfunction "2_2") (pintype "passive"))
      (node (ref "R52") (pin "2") (pinfunction "2_2") (pintype "passive"))
      (node (ref "R53") (pin "2") (pinfunction "2_2") (pintype "passive"))
    )
    (net (code "57") (name "GND") (class "Default")
      (node (ref "C10") (pin "2") (pinfunction "2_2") (pintype "passive"))
      (node (ref "C12") (pin "2") (pinfunction "2_2") (pintype "passive"))
      (node (ref "C15") (pin "1") (pinfunction "1_1") (pintype "passive"))
      (node (ref "C19") (pin "1") (pinfunction "1_1") (pintype "passive"))
      (node (ref "C2") (pin "1") (pinfunction "1_1") (pintype "passive"))
      (node (ref "C23") (pin "1") (pinfunction "1_1") (pintype "passive"))
      (node (ref "C3") (pin "2") (pinfunction "2_2") (pintype "passive"))
      (node (ref "C37") (pin "1") (pinfunction "1_1") (pintype "passive"))
      (node (ref "C43") (pin "1") (pinfunction "1_1") (pintype "passive"))
      (node (ref "C45") (pin "1") (pinfunction "1_1") (pintype "passive"))
      (node (ref "C6") (pin "1") (pinfunction "1_1") (pintype "passive"))
      (node (ref "CE1") (pin "2") (pinfunction "2_2") (pintype "passive"))
      (node (ref "CE3") (pin "2") (pinfunction "2_2") (pintype "passive"))
      (node (ref "CE4") (pin "2") (pinfunction "2_2") (pintype "passive"))
      (node (ref "CE5") (pin "2") (pinfunction "2_2") (pintype "passive"))
      (node (ref "G2") (pin "1") (pinfunction "1_1") (pintype "passive"))
      (node (ref "G4") (pin "1") (pinfunction "1_1") (pintype "passive"))
      (node (ref "G7") (pin "1") (pinfunction "1_1") (pintype "passive"))
      (node (ref "GND") (pin "1") (pinfunction "1_1") (pintype "passive"))
      (node (ref "LED_POWER") (pin "2") (pinfunction "K_2") (pintype "passive"))
      (node (ref "P2") (pin "16") (pinfunction "16_16") (pintype "passive"))
      (node (ref "P2") (pin "27") (pinfunction "27_27") (pintype "passive"))
      (node (ref "P2") (pin "28") (pinfunction "28_28") (pintype "passive"))
      (node (ref "P4") (pin "1") (pinfunction "1_1") (pintype "passive"))
      (node (ref "P8") (pin "1") (pinfunction "1_1") (pintype "passive"))
      (node (ref "R10") (pin "2") (pinfunction "2_2") (pintype "passive"))
      (node (ref "R14") (pin "2") (pinfunction "2_2") (pintype "passive"))
      (node (ref "R35") (pin "2") (pinfunction "2_2") (pintype "passive"))
      (node (ref "R4") (pin "2") (pinfunction "TAP_2") (pintype "passive"))
      (node (ref "R4") (pin "4") (pinfunction "BOT_4") (pintype "passive"))
      (node (ref "R43") (pin "1") (pinfunction "1_1") (pintype "passive"))
      (node (ref "R69") (pin "2") (pinfunction "2_2") (pintype "passive"))
      (node (ref "START") (pin "1") (pinfunction "1_1") (pintype "passive"))
      (node (ref "START") (pin "3") (pinfunction "3_3") (pintype "passive"))
      (node (ref "STOP") (pin "1") (pinfunction "1_1") (pintype "passive"))
      (node (ref "STOP") (pin "3") (pinfunction "3_3") (pintype "passive"))
      (node (ref "U3") (pin "2") (pinfunction "GND_2") (pintype "passive"))
      (node (ref "U4") (pin "1") (pinfunction "GND_1") (pintype "passive"))
    )
    (net (code "58") (name "Net-(D1-K)") (class "Default")
      (node (ref "D1") (pin "2") (pinfunction "K_2") (pintype "passive"))
      (node (ref "R79") (pin "2") (pinfunction "2_2") (pintype "passive"))
    )
    (net (code "59") (name "Net-(D2-K)") (class "Default")
      (node (ref "D2") (pin "2") (pinfunction "K_2") (pintype "passive"))
      (node (ref "R78") (pin "2") (pinfunction "2_2") (pintype "passive"))
    )
    (net (code "60") (name "Net-(D3-A)") (class "Default")
      (node (ref "D3") (pin "1") (pinfunction "A_1") (pintype "passive"))
      (node (ref "R20") (pin "2") (pinfunction "2_2") (pintype "passive"))
    )
    (net (code "61") (name "Net-(D4-K)") (class "Default")
      (node (ref "D4") (pin "2") (pinfunction "K_2") (pintype "passive"))
      (node (ref "R77") (pin "2") (pinfunction "2_2") (pintype "passive"))
    )
    (net (code "62") (name "Net-(D7-A)") (class "Default")
      (node (ref "D7") (pin "1") (pinfunction "A_1") (pintype "passive"))
      (node (ref "R21") (pin "2") (pinfunction "2_2") (pintype "passive"))
    )
    (net (code "63") (name "Net-(D8-A)") (class "Default")
      (node (ref "D8") (pin "1") (pinfunction "A_1") (pintype "passive"))
      (node (ref "R22") (pin "2") (pinfunction "2_2") (pintype "passive"))
    )
    (net (code "64") (name "Net-(D9-A)") (class "Default")
      (node (ref "D9") (pin "1") (pinfunction "A_1") (pintype "passive"))
      (node (ref "R23") (pin "2") (pinfunction "2_2") (pintype "passive"))
    )
    (net (code "65") (name "Net-(D10-A)") (class "Default")
      (node (ref "D10") (pin "1") (pinfunction "A_1") (pintype "passive"))
      (node (ref "R24") (pin "2") (pinfunction "2_2") (pintype "passive"))
    )
    (net (code "66") (name "Net-(D11-A)") (class "Default")
      (node (ref "D11") (pin "1") (pinfunction "A_1") (pintype "passive"))
      (node (ref "R25") (pin "2") (pinfunction "2_2") (pintype "passive"))
    )
    (net (code "67") (name "Net-(D13-K)") (class "Default")
      (node (ref "CE3") (pin "1") (pinfunction "1_1") (pintype "passive"))
      (node (ref "D13") (pin "2") (pinfunction "K_2") (pintype "passive"))
      (node (ref "U4") (pin "5") (pinfunction "DRAIN_5") (pintype "passive"))
    )
    (net (code "68") (name "Net-(LED1-K)") (class "Default")
      (node (ref "LED1") (pin "2") (pinfunction "K_2") (pintype "passive"))
      (node (ref "R10") (pin "1") (pinfunction "1_1") (pintype "passive"))
    )
    (net (code "69") (name "Net-(LED2-K)") (class "Default")
      (node (ref "LED2") (pin "2") (pinfunction "K_2") (pintype "passive"))
      (node (ref "R14") (pin "1") (pinfunction "1_1") (pintype "passive"))
    )
    (net (code "70") (name "Net-(LED3-K)") (class "Default")
      (node (ref "LED3") (pin "2") (pinfunction "K_2") (pintype "passive"))
      (node (ref "R11") (pin "1") (pinfunction "1_1") (pintype "passive"))
    )
    (net (code "71") (name "Net-(LED_POWER-A)") (class "Default")
      (node (ref "LED_POWER") (pin "1") (pinfunction "A_1") (pintype "passive"))
      (node (ref "R65") (pin "2") (pinfunction "2_2") (pintype "passive"))
    )
    (net (code "72") (name "Net-(P4-Pad2)") (class "Default")
      (node (ref "P4") (pin "2") (pinfunction "2_2") (pintype "passive"))
      (node (ref "R12") (pin "1") (pinfunction "1_1") (pintype "passive"))
    )
    (net (code "73") (name "Net-(P4-Pad3)") (class "Default")
      (node (ref "P4") (pin "3") (pinfunction "3_3") (pintype "passive"))
      (node (ref "R9") (pin "2") (pinfunction "2_2") (pintype "passive"))
    )
    (net (code "74") (name "Net-(R1-Pad1)") (class "Default")
      (node (ref "R1") (pin "1") (pinfunction "1_1") (pintype "passive"))
      (node (ref "R55") (pin "2") (pinfunction "2_2") (pintype "passive"))
    )
    (net (code "75") (name "Net-(R2-Pad1)") (class "Default")
      (node (ref "R2") (pin "1") (pinfunction "1_1") (pintype "passive"))
      (node (ref "R59") (pin "2") (pinfunction "2_2") (pintype "passive"))
    )
    (net (code "76") (name "Net-(R3-Pad1)") (class "Default")
      (node (ref "R3") (pin "1") (pinfunction "1_1") (pintype "passive"))
      (node (ref "R61") (pin "2") (pinfunction "2_2") (pintype "passive"))
    )
    (net (code "77") (name "Net-(R74-Pad2)") (class "Default")
      (node (ref "R74") (pin "2") (pinfunction "2_2") (pintype "passive"))
      (node (ref "R75") (pin "1") (pinfunction "1_1") (pintype "passive"))
    )
    (net (code "78") (name "Net-(U3-Vin)") (class "Default")
      (node (ref "R18") (pin "2") (pinfunction "2_2") (pintype "passive"))
      (node (ref "U3") (pin "3") (pinfunction "Vin_3") (pintype "passive"))
    )
    (net (code "79") (name "Net-(U4-CS)") (class "Default")
      (node (ref "R37") (pin "2") (pinfunction "2_2") (pintype "passive"))
      (node (ref "U4") (pin "7") (pinfunction "CS_7") (pintype "passive"))
    )
    (net (code "80") (name "Net-(U4-IC_GND)") (class "Default")
      (node (ref "C4") (pin "2") (pinfunction "2_2") (pintype "passive"))
      (node (ref "PL1") (pin "2") (pinfunction "2_2") (pintype "passive"))
      (node (ref "R37") (pin "1") (pinfunction "1_1") (pintype "passive"))
      (node (ref "U4") (pin "8") (pinfunction "IC_GND_8") (pintype "passive"))
    )
    (net (code "81") (name "Net-(U4-VCC)") (class "Default")
      (node (ref "C4") (pin "1") (pinfunction "1_1") (pintype "passive"))
      (node (ref "U4") (pin "4") (pinfunction "VCC_4") (pintype "passive"))
    )
    (net (code "82") (name "Net-(UH-G)") (class "Default")
      (node (ref "C7") (pin "1") (pinfunction "1_1") (pintype "passive"))
      (node (ref "R20") (pin "1") (pinfunction "1_1") (pintype "passive"))
      (node (ref "R26") (pin "2") (pinfunction "2_2") (pintype "passive"))
      (node (ref "R36") (pin "2") (pinfunction "2_2") (pintype "passive"))
      (node (ref "UH") (pin "1") (pinfunction "G_1") (pintype "passive"))
    )
    (net (code "83") (name "Net-(UL-G)") (class "Default")
      (node (ref "C11") (pin "1") (pinfunction "1_1") (pintype "passive"))
      (node (ref "R21") (pin "1") (pinfunction "1_1") (pintype "passive"))
      (node (ref "R27") (pin "2") (pinfunction "2_2") (pintype "passive"))
      (node (ref "R38") (pin "2") (pinfunction "2_2") (pintype "passive"))
      (node (ref "UL") (pin "1") (pinfunction "G_1") (pintype "passive"))
    )
    (net (code "84") (name "Net-(VH-G)") (class "Default")
      (node (ref "C16") (pin "1") (pinfunction "1_1") (pintype "passive"))
      (node (ref "R22") (pin "1") (pinfunction "1_1") (pintype "passive"))
      (node (ref "R28") (pin "2") (pinfunction "2_2") (pintype "passive"))
      (node (ref "R39") (pin "2") (pinfunction "2_2") (pintype "passive"))
      (node (ref "VH") (pin "1") (pinfunction "G_1") (pintype "passive"))
    )
    (net (code "85") (name "Net-(VL-G)") (class "Default")
      (node (ref "C20") (pin "1") (pinfunction "1_1") (pintype "passive"))
      (node (ref "R23") (pin "1") (pinfunction "1_1") (pintype "passive"))
      (node (ref "R29") (pin "2") (pinfunction "2_2") (pintype "passive"))
      (node (ref "R40") (pin "2") (pinfunction "2_2") (pintype "passive"))
      (node (ref "VL") (pin "1") (pinfunction "G_1") (pintype "passive"))
    )
    (net (code "86") (name "Net-(WH-G)") (class "Default")
      (node (ref "C24") (pin "1") (pinfunction "1_1") (pintype "passive"))
      (node (ref "R24") (pin "1") (pinfunction "1_1") (pintype "passive"))
      (node (ref "R30") (pin "2") (pinfunction "2_2") (pintype "passive"))
      (node (ref "R41") (pin "2") (pinfunction "2_2") (pintype "passive"))
      (node (ref "WH") (pin "1") (pinfunction "G_1") (pintype "passive"))
    )
    (net (code "87") (name "Net-(WL-G)") (class "Default")
      (node (ref "C34") (pin "1") (pinfunction "1_1") (pintype "passive"))
      (node (ref "R25") (pin "1") (pinfunction "1_1") (pintype "passive"))
      (node (ref "R31") (pin "2") (pinfunction "2_2") (pintype "passive"))
      (node (ref "R44") (pin "2") (pinfunction "2_2") (pintype "passive"))
      (node (ref "WL") (pin "1") (pinfunction "G_1") (pintype "passive"))
    )
    (net (code "88") (name "PGND") (class "Default")
      (node (ref "C28") (pin "1") (pinfunction "1_1") (pintype "passive"))
      (node (ref "C29") (pin "1") (pinfunction "1_1") (pintype "passive"))
      (node (ref "C30") (pin "1") (pinfunction "1_1") (pintype "passive"))
      (node (ref "CE2") (pin "2") (pinfunction "2_2") (pintype "passive"))
      (node (ref "G1") (pin "1") (pinfunction "1_1") (pintype "passive"))
      (node (ref "P1") (pin "1") (pinfunction "1_1") (pintype "passive"))
      (node (ref "P1") (pin "2") (pinfunction "2_2") (pintype "passive"))
      (node (ref "P2") (pin "1") (pinfunction "1_1") (pintype "passive"))
      (node (ref "P2") (pin "2") (pinfunction "2_2") (pintype "passive"))
      (node (ref "R15") (pin "2") (pinfunction "2_2") (pintype "passive"))
      (node (ref "R16") (pin "1") (pinfunction "1_1") (pintype "passive"))
      (node (ref "R17") (pin "2") (pinfunction "2_2") (pintype "passive"))
      (node (ref "R32") (pin "1") (pinfunction "1_1") (pintype "passive"))
      (node (ref "R33") (pin "1") (pinfunction "1_1") (pintype "passive"))
      (node (ref "R34") (pin "1") (pinfunction "1_1") (pintype "passive"))
      (node (ref "R49") (pin "2") (pinfunction "2_2") (pintype "passive"))
      (node (ref "R69") (pin "1") (pinfunction "1_1") (pintype "passive"))
    )
    (net (code "89") (name "unconnected-(U4-NC-Pad3)") (class "Default")
      (node (ref "U4") (pin "3") (pinfunction "NC_3") (pintype "passive+no_connect"))
    )
    (net (code "90") (name "unconnected-(U4-NC-Pad6)") (class "Default")
      (node (ref "U4") (pin "6") (pinfunction "NC_6") (pintype "passive+no_connect"))
    )
  )
)
